# ElectronicLoad.net
KiCad netlist of a schematic drawn in Altium Designer
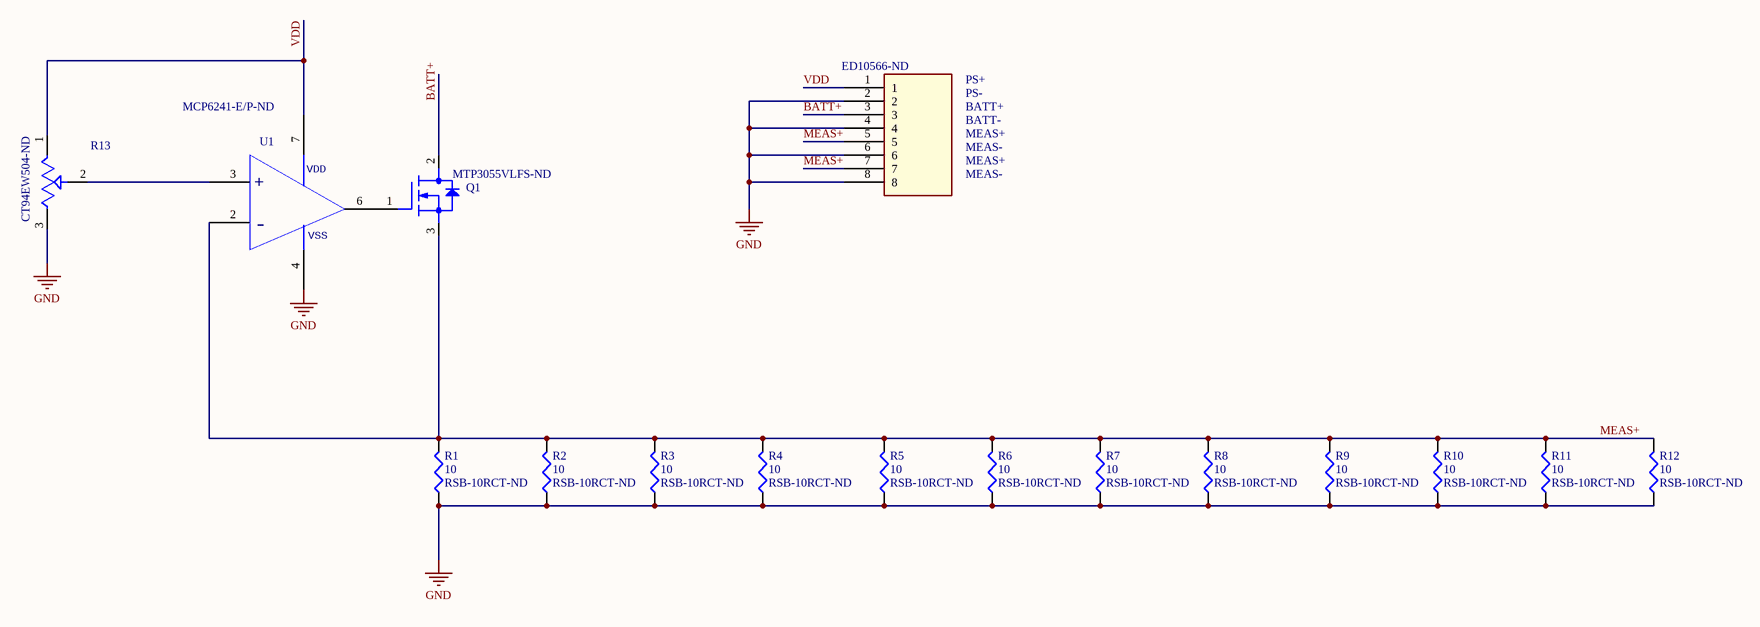
[diagram p0: ElectronicLoad.SchDoc]

(export (version "E")
  (design (tool "Eeschema 10.0.6"))
  (components
    (comp (ref "J1")
      (value "CONN8")
      (footprint "CONN8_8X100")
      (description "Conn Terminal Block 8 POS 2.54mm Solder ST Thru-Hole 6A")
      (fields
        (field (name "SUPPLIER PART NUMBER 1") "ED10566-ND")
        (field (name "MANUFACTURER") "On-Shore Technology")
        (field (name "MANUFACTURER PART NUMBER") "OSTVN08A150")
      )
      (libsource (lib "WaveMode") (part "CONN8"))
    )
    (comp (ref "Q1")
      (value "MTP3055VL")
      (footprint "TO-220-3")
      (description "Transistor MOSFET N Channel 60 Volt 12 Amp 3 Pin TO-220-3")
      (fields
        (field (name "SUPPLIER PART NUMBER 1") "MTP3055VLFS-ND")
        (field (name "MANUFACTURER") "ON Semiconductor / Fairchild")
      )
      (libsource (lib "WaveMode") (part "MTP3055VL"))
    )
    (comp (ref "R1")
      (value "10")
      (footprint "R_ThruHole_3W")
      (description "Res Wirewound 10 Ohm 1% 3W ±20ppm/°C Ceramic Hi Temp Sil AXL Thru-Hole T/R")
      (fields
        (field (name "SUPPLIER PART NUMBER 1") "RSB-10RCT-ND")
        (field (name "MANUFACTURER") "Vishay Dale")
        (field (name "MANUFACTURER PART NUMBER") "RS02B10R00FE70")
        (field (name "PUBLISHER") "Altium Limited")
      )
      (libsource (lib "Miscellaneous Devices") (part "Res3"))
    )
    (comp (ref "R2")
      (value "10")
      (footprint "R_ThruHole_3W")
      (description "Res Wirewound 10 Ohm 1% 3W ±20ppm/°C Ceramic Hi Temp Sil AXL Thru-Hole T/R")
      (fields
        (field (name "SUPPLIER PART NUMBER 1") "RSB-10RCT-ND")
        (field (name "MANUFACTURER") "Vishay Dale")
        (field (name "MANUFACTURER PART NUMBER") "RS02B10R00FE70")
        (field (name "PUBLISHER") "Altium Limited")
      )
      (libsource (lib "Miscellaneous Devices") (part "Res3"))
    )
    (comp (ref "R3")
      (value "10")
      (footprint "R_ThruHole_3W")
      (description "Res Wirewound 10 Ohm 1% 3W ±20ppm/°C Ceramic Hi Temp Sil AXL Thru-Hole T/R")
      (fields
        (field (name "SUPPLIER PART NUMBER 1") "RSB-10RCT-ND")
        (field (name "MANUFACTURER") "Vishay Dale")
        (field (name "MANUFACTURER PART NUMBER") "RS02B10R00FE70")
        (field (name "PUBLISHER") "Altium Limited")
      )
      (libsource (lib "Miscellaneous Devices") (part "Res3"))
    )
    (comp (ref "R4")
      (value "10")
      (footprint "R_ThruHole_3W")
      (description "Res Wirewound 10 Ohm 1% 3W ±20ppm/°C Ceramic Hi Temp Sil AXL Thru-Hole T/R")
      (fields
        (field (name "SUPPLIER PART NUMBER 1") "RSB-10RCT-ND")
        (field (name "MANUFACTURER") "Vishay Dale")
        (field (name "MANUFACTURER PART NUMBER") "RS02B10R00FE70")
        (field (name "PUBLISHER") "Altium Limited")
      )
      (libsource (lib "Miscellaneous Devices") (part "Res3"))
    )
    (comp (ref "R5")
      (value "10")
      (footprint "R_ThruHole_3W")
      (description "Res Wirewound 10 Ohm 1% 3W ±20ppm/°C Ceramic Hi Temp Sil AXL Thru-Hole T/R")
      (fields
        (field (name "SUPPLIER PART NUMBER 1") "RSB-10RCT-ND")
        (field (name "MANUFACTURER") "Vishay Dale")
        (field (name "MANUFACTURER PART NUMBER") "RS02B10R00FE70")
        (field (name "PUBLISHER") "Altium Limited")
      )
      (libsource (lib "Miscellaneous Devices") (part "Res3"))
    )
    (comp (ref "R6")
      (value "10")
      (footprint "R_ThruHole_3W")
      (description "Res Wirewound 10 Ohm 1% 3W ±20ppm/°C Ceramic Hi Temp Sil AXL Thru-Hole T/R")
      (fields
        (field (name "SUPPLIER PART NUMBER 1") "RSB-10RCT-ND")
        (field (name "MANUFACTURER") "Vishay Dale")
        (field (name "MANUFACTURER PART NUMBER") "RS02B10R00FE70")
        (field (name "PUBLISHER") "Altium Limited")
      )
      (libsource (lib "Miscellaneous Devices") (part "Res3"))
    )
    (comp (ref "R7")
      (value "10")
      (footprint "R_ThruHole_3W")
      (description "Res Wirewound 10 Ohm 1% 3W ±20ppm/°C Ceramic Hi Temp Sil AXL Thru-Hole T/R")
      (fields
        (field (name "SUPPLIER PART NUMBER 1") "RSB-10RCT-ND")
        (field (name "MANUFACTURER") "Vishay Dale")
        (field (name "MANUFACTURER PART NUMBER") "RS02B10R00FE70")
        (field (name "PUBLISHER") "Altium Limited")
      )
      (libsource (lib "Miscellaneous Devices") (part "Res3"))
    )
    (comp (ref "R8")
      (value "10")
      (footprint "R_ThruHole_3W")
      (description "Res Wirewound 10 Ohm 1% 3W ±20ppm/°C Ceramic Hi Temp Sil AXL Thru-Hole T/R")
      (fields
        (field (name "SUPPLIER PART NUMBER 1") "RSB-10RCT-ND")
        (field (name "MANUFACTURER") "Vishay Dale")
        (field (name "MANUFACTURER PART NUMBER") "RS02B10R00FE70")
        (field (name "PUBLISHER") "Altium Limited")
      )
      (libsource (lib "Miscellaneous Devices") (part "Res3"))
    )
    (comp (ref "R9")
      (value "10")
      (footprint "R_ThruHole_3W")
      (description "Res Wirewound 10 Ohm 1% 3W ±20ppm/°C Ceramic Hi Temp Sil AXL Thru-Hole T/R")
      (fields
        (field (name "SUPPLIER PART NUMBER 1") "RSB-10RCT-ND")
        (field (name "MANUFACTURER") "Vishay Dale")
        (field (name "MANUFACTURER PART NUMBER") "RS02B10R00FE70")
        (field (name "PUBLISHER") "Altium Limited")
      )
      (libsource (lib "Miscellaneous Devices") (part "Res3"))
    )
    (comp (ref "R10")
      (value "10")
      (footprint "R_ThruHole_3W")
      (description "Res Wirewound 10 Ohm 1% 3W ±20ppm/°C Ceramic Hi Temp Sil AXL Thru-Hole T/R")
      (fields
        (field (name "SUPPLIER PART NUMBER 1") "RSB-10RCT-ND")
        (field (name "MANUFACTURER") "Vishay Dale")
        (field (name "MANUFACTURER PART NUMBER") "RS02B10R00FE70")
        (field (name "PUBLISHER") "Altium Limited")
      )
      (libsource (lib "Miscellaneous Devices") (part "Res3"))
    )
    (comp (ref "R11")
      (value "10")
      (footprint "R_ThruHole_3W")
      (description "Res Wirewound 10 Ohm 1% 3W ±20ppm/°C Ceramic Hi Temp Sil AXL Thru-Hole T/R")
      (fields
        (field (name "SUPPLIER PART NUMBER 1") "RSB-10RCT-ND")
        (field (name "MANUFACTURER") "Vishay Dale")
        (field (name "MANUFACTURER PART NUMBER") "RS02B10R00FE70")
        (field (name "PUBLISHER") "Altium Limited")
      )
      (libsource (lib "Miscellaneous Devices") (part "Res3"))
    )
    (comp (ref "R12")
      (value "10")
      (footprint "R_ThruHole_3W")
      (description "Res Wirewound 10 Ohm 1% 3W ±20ppm/°C Ceramic Hi Temp Sil AXL Thru-Hole T/R")
      (fields
        (field (name "SUPPLIER PART NUMBER 1") "RSB-10RCT-ND")
        (field (name "MANUFACTURER") "Vishay Dale")
        (field (name "MANUFACTURER PART NUMBER") "RS02B10R00FE70")
        (field (name "PUBLISHER") "Altium Limited")
      )
      (libsource (lib "Miscellaneous Devices") (part "Res3"))
    )
    (comp (ref "R13")
      (value "Potentiometer")
      (footprint "VR5")
      (fields
        (field (name "MP") "2-1625931-5")
        (field (name "MF") "TE Connectivity")
        (field (name "SUPPLIER PART NUMBER 1") "CT94EW504-ND")
        (field (name "MANUFACTURER") "Nidec Copal")
      )
      (libsource (lib "WaveMode") (part "Potentiometer"))
    )
    (comp (ref "U1")
      (value "MCP6241")
      (footprint "DIP8")
      (description "IC, Op Amp, Operating Voltage, 1.8 - 5.5V, Outputs, 1, GBWP, 550kHz, PDIP-8")
      (fields
        (field (name "SUPPLIER PART NUMBER 1") "MCP6241-E/P-ND")
        (field (name "MANUFACTURER") "Microchip")
        (field (name "MANUFACTURER PART NUMBER") "MCP6241-E/P")
      )
      (libsource (lib "WaveMode") (part "MCP6241"))
    )
  )
  (nets
    (net (code "1") (name "/BATT+") (class "Default")
      (node (ref "J1") (pin "3") (pinfunction "3_3") (pintype "passive"))
      (node (ref "Q1") (pin "2") (pinfunction "DRAIN_2") (pintype "passive"))
    )
    (net (code "2") (name "/MEAS+") (class "Default")
      (node (ref "J1") (pin "5") (pinfunction "5_5") (pintype "passive"))
      (node (ref "J1") (pin "7") (pinfunction "7_7") (pintype "passive"))
      (node (ref "Q1") (pin "3") (pinfunction "SOURCE_3") (pintype "passive"))
      (node (ref "R1") (pin "2") (pinfunction "2_2") (pintype "passive"))
      (node (ref "R10") (pin "2") (pinfunction "2_2") (pintype "passive"))
      (node (ref "R11") (pin "2") (pinfunction "2_2") (pintype "passive"))
      (node (ref "R12") (pin "2") (pinfunction "2_2") (pintype "passive"))
      (node (ref "R2") (pin "2") (pinfunction "2_2") (pintype "passive"))
      (node (ref "R3") (pin "2") (pinfunction "2_2") (pintype "passive"))
      (node (ref "R4") (pin "2") (pinfunction "2_2") (pintype "passive"))
      (node (ref "R5") (pin "2") (pinfunction "2_2") (pintype "passive"))
      (node (ref "R6") (pin "2") (pinfunction "2_2") (pintype "passive"))
      (node (ref "R7") (pin "2") (pinfunction "2_2") (pintype "passive"))
      (node (ref "R8") (pin "2") (pinfunction "2_2") (pintype "passive"))
      (node (ref "R9") (pin "2") (pinfunction "2_2") (pintype "passive"))
      (node (ref "U1") (pin "2") (pinfunction "IN-_2") (pintype "passive"))
    )
    (net (code "3") (name "/VDD") (class "Default")
      (node (ref "J1") (pin "1") (pinfunction "1_1") (pintype "passive"))
      (node (ref "R13") (pin "1") (pinfunction "1_1") (pintype "passive"))
      (node (ref "U1") (pin "7") (pinfunction "VCC_7") (pintype "passive"))
    )
    (net (code "4") (name "GND") (class "Default")
      (node (ref "J1") (pin "2") (pinfunction "2_2") (pintype "passive"))
      (node (ref "J1") (pin "4") (pinfunction "4_4") (pintype "passive"))
      (node (ref "J1") (pin "6") (pinfunction "6_6") (pintype "passive"))
      (node (ref "J1") (pin "8") (pinfunction "8_8") (pintype "passive"))
      (node (ref "R1") (pin "1") (pinfunction "1_1") (pintype "passive"))
      (node (ref "R10") (pin "1") (pinfunction "1_1") (pintype "passive"))
      (node (ref "R11") (pin "1") (pinfunction "1_1") (pintype "passive"))
      (node (ref "R12") (pin "1") (pinfunction "1_1") (pintype "passive"))
      (node (ref "R13") (pin "3") (pinfunction "3_3") (pintype "passive"))
      (node (ref "R2") (pin "1") (pinfunction "1_1") (pintype "passive"))
      (node (ref "R3") (pin "1") (pinfunction "1_1") (pintype "passive"))
      (node (ref "R4") (pin "1") (pinfunction "1_1") (pintype "passive"))
      (node (ref "R5") (pin "1") (pinfunction "1_1") (pintype "passive"))
      (node (ref "R6") (pin "1") (pinfunction "1_1") (pintype "passive"))
      (node (ref "R7") (pin "1") (pinfunction "1_1") (pintype "passive"))
      (node (ref "R8") (pin "1") (pinfunction "1_1") (pintype "passive"))
      (node (ref "R9") (pin "1") (pinfunction "1_1") (pintype "passive"))
      (node (ref "U1") (pin "4") (pinfunction "VEE_4") (pintype "passive"))
    )
    (net (code "5") (name "Net-(Q1-GATE)") (class "Default")
      (node (ref "Q1") (pin "1") (pinfunction "GATE_1") (pintype "passive"))
      (node (ref "U1") (pin "6") (pinfunction "VOUT_6") (pintype "passive"))
    )
    (net (code "6") (name "Net-(U1-IN+)") (class "Default")
      (node (ref "R13") (pin "2") (pinfunction "2_2") (pintype "passive"))
      (node (ref "U1") (pin "3") (pinfunction "IN+_3") (pintype "passive"))
    )
  )
)
